# power.net
KiCad netlist of a schematic drawn in Altium Designer
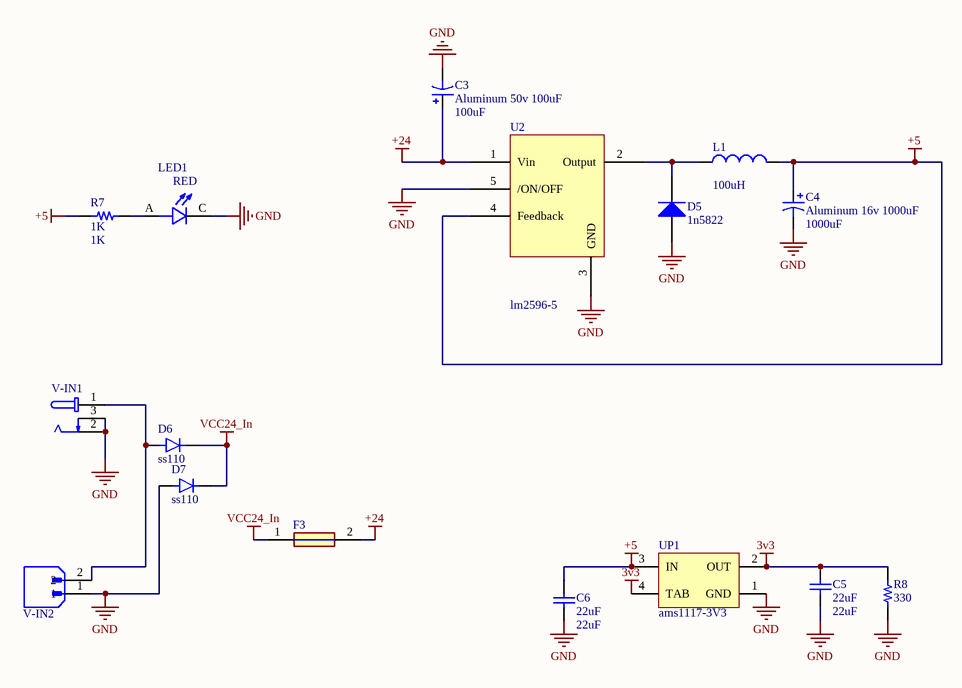
[diagram p0: power.SchDoc]

(export (version "E")
  (design (tool "Eeschema 10.0.6"))
  (components
    (comp (ref "C3")
      (value "Aluminum 50v 100uF")
      (footprint "Cap SMD 100UF 35~50v")
      (description "CAP POLAR SMD")
      (fields (field (name "ALTIUM_VALUE") "100uF") (field (name "PUBLISHER") "Altium Limited"))
      (libsource (lib "Miscellaneous Devices") (part "Cap Pol1"))
    )
    (comp (ref "C4")
      (value "Aluminum 16v 1000uF")
      (footprint "CAP SMD 1000UF 16V")
      (description "CAP POLAR SMD")
      (fields (field (name "ALTIUM_VALUE") "1000uF") (field (name "PUBLISHER") "Altium Limited"))
      (libsource (lib "Miscellaneous Devices") (part "Cap Pol1"))
    )
    (comp (ref "C5")
      (value "22uF")
      (footprint "0603C")
      (description "CAP SMD 0603")
      (fields (field (name "ALTIUM_VALUE") "22uF") (field (name "PUBLISHER") "Altium Limited"))
      (libsource (lib "Miscellaneous Devices") (part "Cap"))
    )
    (comp (ref "C6")
      (value "22uF")
      (footprint "0603C")
      (description "CAP SMD 0603")
      (fields (field (name "ALTIUM_VALUE") "22uF") (field (name "PUBLISHER") "Altium Limited"))
      (libsource (lib "Miscellaneous Devices") (part "Cap"))
    )
    (comp (ref "D5")
      (value "1n5822")
      (footprint "SMA DIODE 2")
      (description "1 Amp schottky Diode SMA")
      (fields (field (name "PUBLISHER") "Altium Limited"))
      (libsource (lib "Miscellaneous Devices") (part "Diode 1N4007"))
    )
    (comp (ref "D6")
      (value "ss110")
      (footprint "ss110")
      (description "Diode Super Barrier 60V 500mA Surface Mount SOD-123")
      (fields (field (name "MP") "SBR0560S1-7") (field (name "MF") "Diodes Inc."))
      (libsource (lib "diode") (part "SBR0560S1-7"))
    )
    (comp (ref "D7")
      (value "ss110")
      (footprint "ss110")
      (description "Diode Super Barrier 60V 500mA Surface Mount SOD-123")
      (fields (field (name "MP") "SBR0560S1-7") (field (name "MF") "Diodes Inc."))
      (libsource (lib "diode") (part "SBR0560S1-7"))
    )
    (comp (ref "F3")
      (value "fuse 2amp")
      (footprint "1206 FUSE")
      (description "Fuse 1206")
      (fields (field (name "MANUFACTURER_PART_NUMBER") "1206SFS200F/63-2"))
      (libsource (lib "robot1") (part "1206SFS200F_63-2"))
    )
    (comp (ref "L1")
      (value "100uH")
      (footprint "inductor")
      (description "Inductor 12*12mm SMD")
      (fields (field (name "Comment") "inductor 100uH") (field (name "PUBLISHER") "Altium Limited"))
      (libsource (lib "Miscellaneous Devices") (part "Inductor"))
    )
    (comp (ref "LED1")
      (value "LED RED")
      (footprint "LED_7012X1")
      (description "LED SMD 0805 RED")
      (fields (field (name "MP") "7012X1"))
      (libsource (lib "LED0805") (part "7012X1"))
    )
    (comp (ref "R7")
      (value "1K")
      (footprint "0603R")
      (description "RES SMD 0603")
      (fields (field (name "PART NUMBER") "RCS0805100KFKEA") (field (name "ALTIUM_VALUE") "1K"))
      (libsource (lib "lamp control-ver2") (part "Resistor"))
    )
    (comp (ref "R8")
      (value "330")
      (footprint "0603R")
      (description "RES SMD 0603")
      (fields (field (name "PART NUMBER") "RCS0805100KFKEA"))
      (libsource (lib "lamp control-ver2") (part "Resistor"))
    )
    (comp (ref "U2") (value "lm2596-5") (footprint "2596") (libsource (lib "No.2") (part "lm2596")))
    (comp (ref "UP1")
      (value "ams1117-3V3")
      (footprint "SOT223")
      (description "3.3 Volt, 800mA SOT-223")
      (fields (field (name "DESIGNER") "Ali Hafizi"))
      (libsource (lib "Altium (2)") (part "AMS1117-x.x"))
    )
    (comp (ref "V-IN1")
      (value "DC jack power")
      (footprint "GCT_DCJ235-05-A-XX-X_REVA")
      (description "Dc Power Jack on-board")
      (fields (field (name "MF") "Global Connector Technology") (field (name "MP") "DCJ235-05-A-K1-A"))
      (libsource (lib "DCJ235-05-A-XX-X_REVA") (part "DCJ235-05-A-XX-X_REVA"))
    )
    (comp (ref "V-IN2")
      (value "Phoenix")
      (footprint "AMPHENOL_OQ0271510000G")
      (description "Phoenix Terminal Right 2PIN")
      (fields (field (name "MP") "OQ0271510000G") (field (name "MF") "Amphenol Anytek"))
      (libsource (lib "phoenix2") (part "OQ0271510000G"))
    )
  )
  (nets
    (net (code "1") (name "+5") (class "Default")
      (node (ref "C4") (pin "1") (pinfunction "1_1") (pintype "passive"))
      (node (ref "C6") (pin "2") (pinfunction "2_2") (pintype "passive"))
      (node (ref "L1") (pin "2") (pinfunction "2_2") (pintype "passive"))
      (node (ref "R7") (pin "1") (pinfunction "1_1") (pintype "passive"))
      (node (ref "U2") (pin "4") (pinfunction "Feedback_4") (pintype "power_in"))
      (node (ref "UP1") (pin "3") (pinfunction "IN_3") (pintype "power_in"))
    )
    (net (code "2") (name "+24") (class "Default")
      (node (ref "C3") (pin "1") (pinfunction "1_1") (pintype "passive"))
      (node (ref "F3") (pin "2") (pinfunction "2_2") (pintype "passive"))
      (node (ref "U2") (pin "1") (pinfunction "Vin_1") (pintype "power_in"))
    )
    (net (code "3") (name "3v3") (class "Default")
      (node (ref "C5") (pin "2") (pinfunction "2_2") (pintype "passive"))
      (node (ref "R8") (pin "1") (pinfunction "1_1") (pintype "passive"))
      (node (ref "UP1") (pin "2") (pinfunction "OUT_2") (pintype "power_in"))
      (node (ref "UP1") (pin "4") (pinfunction "TAB_4") (pintype "power_in"))
    )
    (net (code "4") (name "GND") (class "Default")
      (node (ref "C3") (pin "2") (pinfunction "2_2") (pintype "passive"))
      (node (ref "C4") (pin "2") (pinfunction "2_2") (pintype "passive"))
      (node (ref "C5") (pin "1") (pinfunction "1_1") (pintype "passive"))
      (node (ref "C6") (pin "1") (pinfunction "1_1") (pintype "passive"))
      (node (ref "D5") (pin "1") (pinfunction "A_1") (pintype "passive"))
      (node (ref "D7") (pin "A") (pinfunction "A_A") (pintype "passive"))
      (node (ref "LED1") (pin "C") (pinfunction "C_C") (pintype "passive"))
      (node (ref "R8") (pin "2") (pinfunction "2_2") (pintype "passive"))
      (node (ref "U2") (pin "3") (pinfunction "GND_3") (pintype "power_in"))
      (node (ref "U2") (pin "5") (pinfunction "/ON/OFF_5") (pintype "power_in"))
      (node (ref "UP1") (pin "1") (pinfunction "GND_1") (pintype "power_in"))
      (node (ref "V-IN1") (pin "2") (pinfunction "2_2") (pintype "passive"))
      (node (ref "V-IN1") (pin "3") (pinfunction "3_3") (pintype "passive"))
      (node (ref "V-IN2") (pin "1") (pinfunction "1_1") (pintype "passive"))
    )
    (net (code "5") (name "Net-(D5-K)") (class "Default")
      (node (ref "D5") (pin "2") (pinfunction "K_2") (pintype "passive"))
      (node (ref "L1") (pin "1") (pinfunction "1_1") (pintype "passive"))
      (node (ref "U2") (pin "2") (pinfunction "Output_2") (pintype "power_in"))
    )
    (net (code "6") (name "Net-(D6-PadA)") (class "Default")
      (node (ref "D6") (pin "A") (pinfunction "A_A") (pintype "passive"))
      (node (ref "V-IN1") (pin "1") (pinfunction "1_1") (pintype "passive"))
      (node (ref "V-IN2") (pin "2") (pinfunction "2_2") (pintype "passive"))
    )
    (net (code "7") (name "Net-(LED1-PadA)") (class "Default")
      (node (ref "LED1") (pin "A") (pinfunction "A_A") (pintype "passive"))
      (node (ref "R7") (pin "2") (pinfunction "2_2") (pintype "passive"))
    )
    (net (code "8") (name "VCC24_In") (class "Default")
      (node (ref "D6") (pin "C") (pinfunction "K_C") (pintype "passive"))
      (node (ref "D7") (pin "C") (pinfunction "K_C") (pintype "passive"))
      (node (ref "F3") (pin "1") (pinfunction "1_1") (pintype "passive"))
    )
  )
)
